# Kar_PCB.net
KiCad netlist of a schematic drawn in Altium Designer
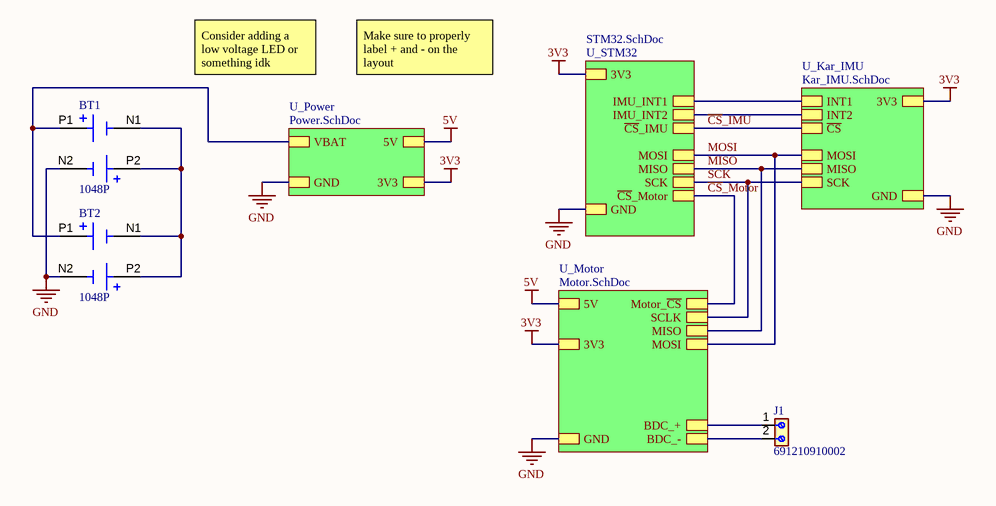
[diagram p0: Kar_PCB.SchDoc]

(export (version "E")
  (design (tool "Eeschema 10.0.6"))
  (components
    (comp (ref "BT1")
      (value "1048P")
      (footprint "BAT_1048P")
      (description "SMT Polarized Holder for Dual 18650 Batteries")
      (fields (field (name "MF") "Keystone Electronics"))
      (libsource (lib "1048P") (part "1048P"))
    )
    (comp (ref "BT2")
      (value "1048P")
      (footprint "BAT_1048P")
      (description "SMT Polarized Holder for Dual 18650 Batteries")
      (fields (field (name "MF") "Keystone Electronics"))
      (libsource (lib "1048P") (part "1048P"))
    )
    (comp (ref "J1")
      (value "691210910002")
      (footprint "691210910002")
      (fields (field (name "MF") "{'manufacturer': u'~{W}xfcrth Elektronik'}"))
      (libsource (lib "691210910002") (part "691210910002"))
    )
  )
  (nets
    (net (code "1") (name "/BDC_+") (class "Default")
      (node (ref "J1") (pin "1") (pinfunction "1_1") (pintype "passive"))
    )
    (net (code "2") (name "/BDC_-") (class "Default")
      (node (ref "J1") (pin "2") (pinfunction "2_2") (pintype "passive"))
    )
    (net (code "8") (name "/VBAT") (class "Default")
      (node (ref "BT1") (pin "P1") (pinfunction "P1_P1") (pintype "passive"))
      (node (ref "BT2") (pin "P1") (pinfunction "P1_P1") (pintype "passive"))
    )
    (net (code "13") (name "GND") (class "Default")
      (node (ref "BT1") (pin "N2") (pinfunction "N2_N2") (pintype "passive"))
      (node (ref "BT2") (pin "N2") (pinfunction "N2_N2") (pintype "passive"))
    )
    (net (code "14") (name "Net-(BT1-PadN1)") (class "Default")
      (node (ref "BT1") (pin "N1") (pinfunction "N1_N1") (pintype "passive"))
      (node (ref "BT1") (pin "P2") (pinfunction "P2_P2") (pintype "passive"))
      (node (ref "BT2") (pin "N1") (pinfunction "N1_N1") (pintype "passive"))
      (node (ref "BT2") (pin "P2") (pinfunction "P2_P2") (pintype "passive"))
    )
  )
)
